# G22V1.net
KiCad netlist of a schematic drawn in EAGLE
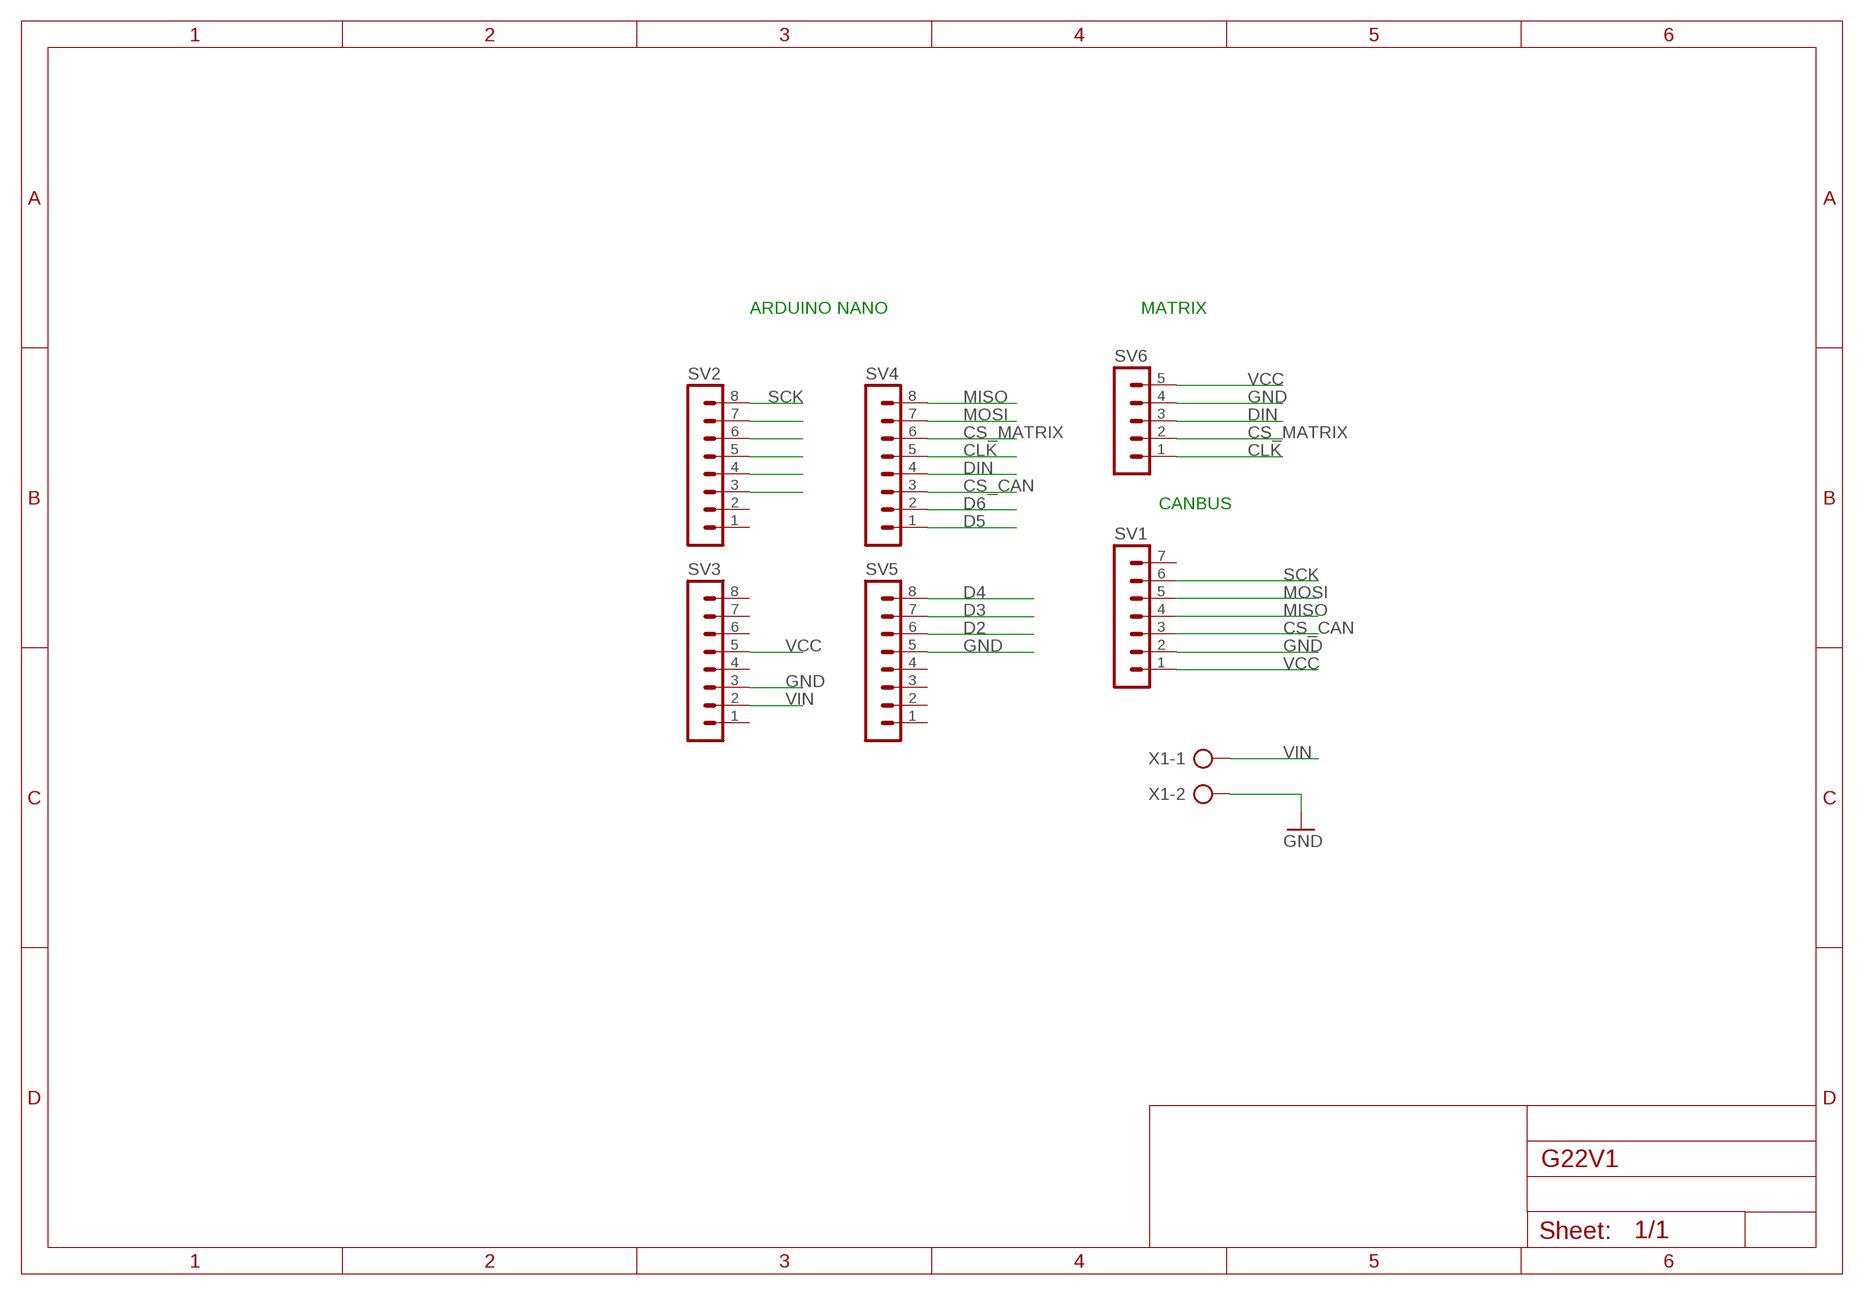
[diagram p0: schematic, sheet 1]

(export (version "E")
  (design (tool "Eeschema 10.0.6"))
  (components
    (comp (ref "SV1")
      (value "MA07-1")
      (footprint "eagle-import:MA07-1")
      (libsource (lib "eagle-import") (part "MA07-1"))
    )
    (comp (ref "SV2")
      (value "MA08-1")
      (footprint "eagle-import:MA08-1")
      (libsource (lib "eagle-import") (part "MA08-1"))
    )
    (comp (ref "SV3")
      (value "MA08-1")
      (footprint "eagle-import:MA08-1")
      (libsource (lib "eagle-import") (part "MA08-1"))
    )
    (comp (ref "SV4")
      (value "MA08-1")
      (footprint "eagle-import:MA08-1")
      (libsource (lib "eagle-import") (part "MA08-1"))
    )
    (comp (ref "SV5")
      (value "MA08-1")
      (footprint "eagle-import:MA08-1")
      (libsource (lib "eagle-import") (part "MA08-1"))
    )
    (comp (ref "SV6")
      (value "MA05-1")
      (footprint "eagle-import:MA05-1")
      (libsource (lib "eagle-import") (part "MA05-1"))
    )
    (comp (ref "X1")
      (value "AK300/2")
      (footprint "eagle-import:AK300_2")
      (libsource (lib "eagle-import") (part "AK300/2"))
    )
  )
  (nets
    (net (code "1") (name "/CLK") (class "Default")
      (node (ref "SV4") (pin "5") (pinfunction "5_5") (pintype "passive"))
      (node (ref "SV6") (pin "1") (pinfunction "1_1") (pintype "passive"))
    )
    (net (code "2") (name "/CS_CAN") (class "Default")
      (node (ref "SV1") (pin "3") (pinfunction "3_3") (pintype "passive"))
      (node (ref "SV4") (pin "3") (pinfunction "3_3") (pintype "passive"))
    )
    (net (code "3") (name "/CS_MATRIX") (class "Default")
      (node (ref "SV4") (pin "6") (pinfunction "6_6") (pintype "passive"))
      (node (ref "SV6") (pin "2") (pinfunction "2_2") (pintype "passive"))
    )
    (net (code "4") (name "/D2") (class "Default")
      (node (ref "SV5") (pin "6") (pinfunction "6_6") (pintype "passive"))
    )
    (net (code "5") (name "/D3") (class "Default")
      (node (ref "SV5") (pin "7") (pinfunction "7_7") (pintype "passive"))
    )
    (net (code "6") (name "/D4") (class "Default")
      (node (ref "SV5") (pin "8") (pinfunction "8_8") (pintype "passive"))
    )
    (net (code "7") (name "/D5") (class "Default")
      (node (ref "SV4") (pin "1") (pinfunction "1_1") (pintype "passive"))
    )
    (net (code "8") (name "/D6") (class "Default")
      (node (ref "SV4") (pin "2") (pinfunction "2_2") (pintype "passive"))
    )
    (net (code "9") (name "/DIN") (class "Default")
      (node (ref "SV4") (pin "4") (pinfunction "4_4") (pintype "passive"))
      (node (ref "SV6") (pin "3") (pinfunction "3_3") (pintype "passive"))
    )
    (net (code "10") (name "/MISO") (class "Default")
      (node (ref "SV1") (pin "4") (pinfunction "4_4") (pintype "passive"))
      (node (ref "SV4") (pin "8") (pinfunction "8_8") (pintype "passive"))
    )
    (net (code "11") (name "/MOSI") (class "Default")
      (node (ref "SV1") (pin "5") (pinfunction "5_5") (pintype "passive"))
      (node (ref "SV4") (pin "7") (pinfunction "7_7") (pintype "passive"))
    )
    (net (code "12") (name "/SCK") (class "Default")
      (node (ref "SV1") (pin "6") (pinfunction "6_6") (pintype "passive"))
      (node (ref "SV2") (pin "8") (pinfunction "8_8") (pintype "passive"))
    )
    (net (code "13") (name "/VCC") (class "Default")
      (node (ref "SV1") (pin "1") (pinfunction "1_1") (pintype "passive"))
      (node (ref "SV3") (pin "5") (pinfunction "5_5") (pintype "passive"))
      (node (ref "SV6") (pin "5") (pinfunction "5_5") (pintype "passive"))
    )
    (net (code "14") (name "/VIN") (class "Default")
      (node (ref "SV3") (pin "2") (pinfunction "2_2") (pintype "passive"))
      (node (ref "X1") (pin "1") (pinfunction "KL_1") (pintype "passive"))
    )
    (net (code "15") (name "GND") (class "Default")
      (node (ref "SV1") (pin "2") (pinfunction "2_2") (pintype "passive"))
      (node (ref "SV3") (pin "3") (pinfunction "3_3") (pintype "passive"))
      (node (ref "SV5") (pin "5") (pinfunction "5_5") (pintype "passive"))
      (node (ref "SV6") (pin "4") (pinfunction "4_4") (pintype "passive"))
      (node (ref "X1") (pin "2") (pinfunction "KL_2") (pintype "passive"))
    )
    (net (code "16") (name "unconnected-(SV1-Pad7)") (class "Default")
      (node (ref "SV1") (pin "7") (pinfunction "7_7") (pintype "passive"))
    )
    (net (code "17") (name "unconnected-(SV2-Pad1)") (class "Default")
      (node (ref "SV2") (pin "1") (pinfunction "1_1") (pintype "passive"))
    )
    (net (code "18") (name "unconnected-(SV2-Pad2)") (class "Default")
      (node (ref "SV2") (pin "2") (pinfunction "2_2") (pintype "passive"))
    )
    (net (code "19") (name "unconnected-(SV2-Pad3)") (class "Default")
      (node (ref "SV2") (pin "3") (pinfunction "3_3") (pintype "passive"))
    )
    (net (code "20") (name "unconnected-(SV2-Pad4)") (class "Default")
      (node (ref "SV2") (pin "4") (pinfunction "4_4") (pintype "passive"))
    )
    (net (code "21") (name "unconnected-(SV2-Pad5)") (class "Default")
      (node (ref "SV2") (pin "5") (pinfunction "5_5") (pintype "passive"))
    )
    (net (code "22") (name "unconnected-(SV2-Pad6)") (class "Default")
      (node (ref "SV2") (pin "6") (pinfunction "6_6") (pintype "passive"))
    )
    (net (code "23") (name "unconnected-(SV2-Pad7)") (class "Default")
      (node (ref "SV2") (pin "7") (pinfunction "7_7") (pintype "passive"))
    )
    (net (code "24") (name "unconnected-(SV3-Pad1)") (class "Default")
      (node (ref "SV3") (pin "1") (pinfunction "1_1") (pintype "passive"))
    )
    (net (code "25") (name "unconnected-(SV3-Pad4)") (class "Default")
      (node (ref "SV3") (pin "4") (pinfunction "4_4") (pintype "passive"))
    )
    (net (code "26") (name "unconnected-(SV3-Pad6)") (class "Default")
      (node (ref "SV3") (pin "6") (pinfunction "6_6") (pintype "passive"))
    )
    (net (code "27") (name "unconnected-(SV3-Pad7)") (class "Default")
      (node (ref "SV3") (pin "7") (pinfunction "7_7") (pintype "passive"))
    )
    (net (code "28") (name "unconnected-(SV3-Pad8)") (class "Default")
      (node (ref "SV3") (pin "8") (pinfunction "8_8") (pintype "passive"))
    )
    (net (code "29") (name "unconnected-(SV5-Pad1)") (class "Default")
      (node (ref "SV5") (pin "1") (pinfunction "1_1") (pintype "passive"))
    )
    (net (code "30") (name "unconnected-(SV5-Pad2)") (class "Default")
      (node (ref "SV5") (pin "2") (pinfunction "2_2") (pintype "passive"))
    )
    (net (code "31") (name "unconnected-(SV5-Pad3)") (class "Default")
      (node (ref "SV5") (pin "3") (pinfunction "3_3") (pintype "passive"))
    )
    (net (code "32") (name "unconnected-(SV5-Pad4)") (class "Default")
      (node (ref "SV5") (pin "4") (pinfunction "4_4") (pintype "passive"))
    )
  )
)
